# RC_Engine_Sound_ESP32.net
KiCad netlist of a schematic drawn in EAGLE
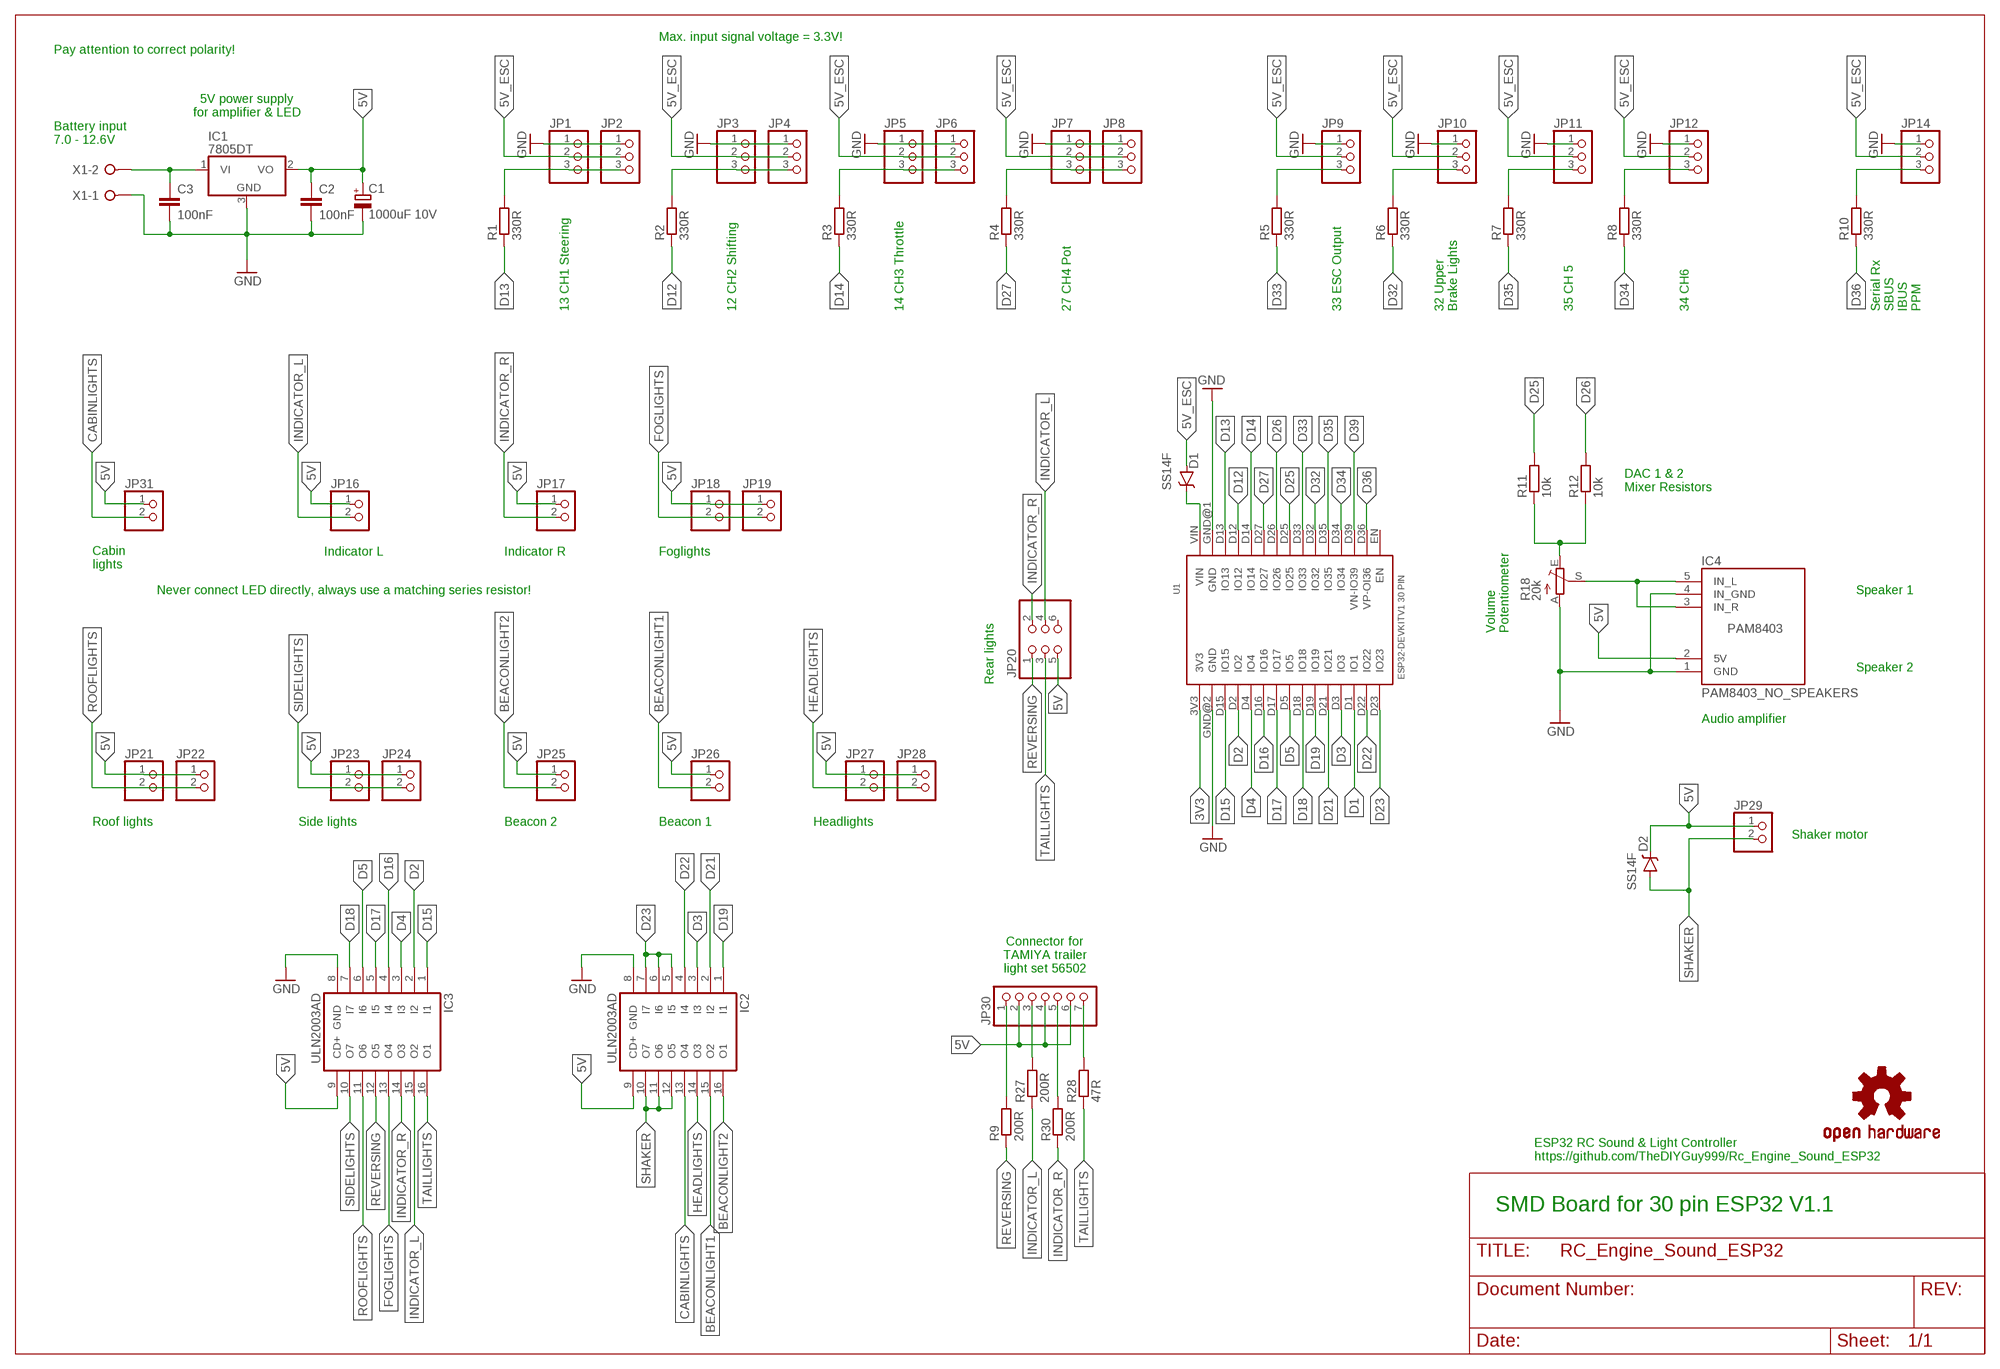
[diagram p0: schematic, sheet 1]

(export (version "E")
  (design (tool "Eeschema 10.0.6"))
  (components
    (comp (ref "C1")
      (value "1000uF 10V")
      (footprint "eagle-import:UD-10X10_NICHICON")
      (libsource (lib "eagle-import") (part "CPOL-EUUD-10X10"))
    )
    (comp (ref "C2")
      (value "100nF")
      (footprint "eagle-import:C0805")
      (libsource (lib "eagle-import") (part "C-EUC0805"))
    )
    (comp (ref "C3")
      (value "100nF")
      (footprint "eagle-import:C0805")
      (libsource (lib "eagle-import") (part "C-EUC0805"))
    )
    (comp (ref "D1")
      (value "SS14F")
      (footprint "eagle-import:SMA-DIODE")
      (libsource (lib "eagle-import") (part "MBRA140"))
    )
    (comp (ref "D2")
      (value "SS14F")
      (footprint "eagle-import:SMA-DIODE")
      (libsource (lib "eagle-import") (part "MBRA140"))
    )
    (comp (ref "IC1")
      (value "7805DT")
      (footprint "eagle-import:TO252")
      (libsource (lib "eagle-import") (part "78DT05"))
    )
    (comp (ref "IC2")
      (value "ULN2003AD")
      (footprint "eagle-import:SO16")
      (libsource (lib "eagle-import") (part "ULN2003AD"))
    )
    (comp (ref "IC3")
      (value "ULN2003AD")
      (footprint "eagle-import:SO16")
      (libsource (lib "eagle-import") (part "ULN2003AD"))
    )
    (comp (ref "IC4")
      (value "PAM8403_NO_SPEAKERS")
      (footprint "eagle-import:PAM8403_NO_SPEAKERS")
      (libsource (lib "eagle-import") (part "PAM8403_NO_SPEAKERS"))
    )
    (comp (ref "JP1")
      (value "PINHD-1X3")
      (footprint "eagle-import:1X03")
      (libsource (lib "eagle-import") (part "PINHD-1X3"))
    )
    (comp (ref "JP2")
      (value "PINHD-1X3")
      (footprint "eagle-import:1X03")
      (libsource (lib "eagle-import") (part "PINHD-1X3"))
    )
    (comp (ref "JP3")
      (value "PINHD-1X3")
      (footprint "eagle-import:1X03")
      (libsource (lib "eagle-import") (part "PINHD-1X3"))
    )
    (comp (ref "JP4")
      (value "PINHD-1X3")
      (footprint "eagle-import:1X03")
      (libsource (lib "eagle-import") (part "PINHD-1X3"))
    )
    (comp (ref "JP5")
      (value "PINHD-1X3")
      (footprint "eagle-import:1X03")
      (libsource (lib "eagle-import") (part "PINHD-1X3"))
    )
    (comp (ref "JP6")
      (value "PINHD-1X3")
      (footprint "eagle-import:1X03")
      (libsource (lib "eagle-import") (part "PINHD-1X3"))
    )
    (comp (ref "JP7")
      (value "PINHD-1X3")
      (footprint "eagle-import:1X03")
      (libsource (lib "eagle-import") (part "PINHD-1X3"))
    )
    (comp (ref "JP8")
      (value "PINHD-1X3")
      (footprint "eagle-import:1X03")
      (libsource (lib "eagle-import") (part "PINHD-1X3"))
    )
    (comp (ref "JP9")
      (value "PINHD-1X3")
      (footprint "eagle-import:1X03")
      (libsource (lib "eagle-import") (part "PINHD-1X3"))
    )
    (comp (ref "JP10")
      (value "PINHD-1X3")
      (footprint "eagle-import:1X03")
      (libsource (lib "eagle-import") (part "PINHD-1X3"))
    )
    (comp (ref "JP11")
      (value "PINHD-1X3")
      (footprint "eagle-import:1X03")
      (libsource (lib "eagle-import") (part "PINHD-1X3"))
    )
    (comp (ref "JP12")
      (value "PINHD-1X3")
      (footprint "eagle-import:1X03")
      (libsource (lib "eagle-import") (part "PINHD-1X3"))
    )
    (comp (ref "JP14")
      (value "PINHD-1X3")
      (footprint "eagle-import:1X03")
      (libsource (lib "eagle-import") (part "PINHD-1X3"))
    )
    (comp (ref "JP16")
      (value "PINHD-1X2")
      (footprint "eagle-import:1X02")
      (libsource (lib "eagle-import") (part "PINHD-1X2"))
    )
    (comp (ref "JP17")
      (value "PINHD-1X2")
      (footprint "eagle-import:1X02")
      (libsource (lib "eagle-import") (part "PINHD-1X2"))
    )
    (comp (ref "JP18")
      (value "PINHD-1X2")
      (footprint "eagle-import:1X02")
      (libsource (lib "eagle-import") (part "PINHD-1X2"))
    )
    (comp (ref "JP19")
      (value "PINHD-1X2")
      (footprint "eagle-import:1X02")
      (libsource (lib "eagle-import") (part "PINHD-1X2"))
    )
    (comp (ref "JP20")
      (value "PINHD-2X3")
      (footprint "eagle-import:2X03")
      (libsource (lib "eagle-import") (part "PINHD-2X3"))
    )
    (comp (ref "JP21")
      (value "PINHD-1X2")
      (footprint "eagle-import:1X02")
      (libsource (lib "eagle-import") (part "PINHD-1X2"))
    )
    (comp (ref "JP22")
      (value "PINHD-1X2")
      (footprint "eagle-import:1X02")
      (libsource (lib "eagle-import") (part "PINHD-1X2"))
    )
    (comp (ref "JP23")
      (value "PINHD-1X2")
      (footprint "eagle-import:1X02")
      (libsource (lib "eagle-import") (part "PINHD-1X2"))
    )
    (comp (ref "JP24")
      (value "PINHD-1X2")
      (footprint "eagle-import:1X02")
      (libsource (lib "eagle-import") (part "PINHD-1X2"))
    )
    (comp (ref "JP25")
      (value "PINHD-1X2")
      (footprint "eagle-import:1X02")
      (libsource (lib "eagle-import") (part "PINHD-1X2"))
    )
    (comp (ref "JP26")
      (value "PINHD-1X2")
      (footprint "eagle-import:1X02")
      (libsource (lib "eagle-import") (part "PINHD-1X2"))
    )
    (comp (ref "JP27")
      (value "PINHD-1X2")
      (footprint "eagle-import:1X02")
      (libsource (lib "eagle-import") (part "PINHD-1X2"))
    )
    (comp (ref "JP28")
      (value "PINHD-1X2")
      (footprint "eagle-import:1X02")
      (libsource (lib "eagle-import") (part "PINHD-1X2"))
    )
    (comp (ref "JP29")
      (value "PINHD-1X2")
      (footprint "eagle-import:1X02")
      (libsource (lib "eagle-import") (part "PINHD-1X2"))
    )
    (comp (ref "JP30")
      (value "PINHD-1X7")
      (footprint "eagle-import:1X07")
      (libsource (lib "eagle-import") (part "PINHD-1X7"))
    )
    (comp (ref "JP31")
      (value "PINHD-1X2")
      (footprint "eagle-import:1X02")
      (libsource (lib "eagle-import") (part "PINHD-1X2"))
    )
    (comp (ref "LOGO1")
      (value "OSHW-LOGOM")
      (footprint "eagle-import:OSHW-LOGO-M")
      (libsource (lib "eagle-import") (part "OSHW-LOGOM"))
    )
    (comp (ref "R1")
      (value "330R")
      (footprint "eagle-import:R0805")
      (libsource (lib "eagle-import") (part "R-EU_R0805"))
    )
    (comp (ref "R2")
      (value "330R")
      (footprint "eagle-import:R0805")
      (libsource (lib "eagle-import") (part "R-EU_R0805"))
    )
    (comp (ref "R3")
      (value "330R")
      (footprint "eagle-import:R0805")
      (libsource (lib "eagle-import") (part "R-EU_R0805"))
    )
    (comp (ref "R4")
      (value "330R")
      (footprint "eagle-import:R0805")
      (libsource (lib "eagle-import") (part "R-EU_R0805"))
    )
    (comp (ref "R5")
      (value "330R")
      (footprint "eagle-import:R0805")
      (libsource (lib "eagle-import") (part "R-EU_R0805"))
    )
    (comp (ref "R6")
      (value "330R")
      (footprint "eagle-import:R0805")
      (libsource (lib "eagle-import") (part "R-EU_R0805"))
    )
    (comp (ref "R7")
      (value "330R")
      (footprint "eagle-import:R0805")
      (libsource (lib "eagle-import") (part "R-EU_R0805"))
    )
    (comp (ref "R8")
      (value "330R")
      (footprint "eagle-import:R0805")
      (libsource (lib "eagle-import") (part "R-EU_R0805"))
    )
    (comp (ref "R9")
      (value "200R")
      (footprint "eagle-import:R0805")
      (libsource (lib "eagle-import") (part "R-EU_R0805"))
    )
    (comp (ref "R10")
      (value "330R")
      (footprint "eagle-import:R0805")
      (libsource (lib "eagle-import") (part "R-EU_R0805"))
    )
    (comp (ref "R11")
      (value "10k")
      (footprint "eagle-import:R0805")
      (libsource (lib "eagle-import") (part "R-EU_R0805"))
    )
    (comp (ref "R12")
      (value "10k")
      (footprint "eagle-import:R0805")
      (libsource (lib "eagle-import") (part "R-EU_R0805"))
    )
    (comp (ref "R18")
      (value "20k")
      (footprint "eagle-import:S64W")
      (libsource (lib "eagle-import") (part "TRIM_EU-S64W"))
    )
    (comp (ref "R27")
      (value "200R")
      (footprint "eagle-import:R0805")
      (libsource (lib "eagle-import") (part "R-EU_R0805"))
    )
    (comp (ref "R28")
      (value "47R")
      (footprint "eagle-import:R0805")
      (libsource (lib "eagle-import") (part "R-EU_R0805"))
    )
    (comp (ref "R30")
      (value "200R")
      (footprint "eagle-import:R0805")
      (libsource (lib "eagle-import") (part "R-EU_R0805"))
    )
    (comp (ref "U1")
      (value "ESP32DEVKITV1")
      (footprint "eagle-import:ESP32-DEVKITV1")
      (libsource (lib "eagle-import") (part "ESP32DEVKITV1"))
    )
    (comp (ref "X1")
      (value "W237-02P")
      (footprint "eagle-import:W237-132")
      (libsource (lib "eagle-import") (part "W237-02P"))
    )
  )
  (nets
    (net (code "1") (name "3V3") (class "Default")
      (node (ref "U1") (pin "3V3") (pinfunction "3V3_3V3") (pintype "bidirectional"))
    )
    (net (code "2") (name "5V") (class "Default")
      (node (ref "C1") (pin "+") (pinfunction "+_+") (pintype "passive"))
      (node (ref "C2") (pin "1") (pinfunction "1_1") (pintype "passive"))
      (node (ref "D2") (pin "C") (pinfunction "C_C") (pintype "passive"))
      (node (ref "IC1") (pin "2") (pinfunction "VO_2") (pintype "passive"))
      (node (ref "IC2") (pin "9") (pinfunction "CD+_9") (pintype "passive"))
      (node (ref "IC3") (pin "9") (pinfunction "CD+_9") (pintype "passive"))
      (node (ref "IC4") (pin "2") (pinfunction "5V_2") (pintype "input"))
      (node (ref "JP16") (pin "1") (pinfunction "1_1") (pintype "passive"))
      (node (ref "JP17") (pin "1") (pinfunction "1_1") (pintype "passive"))
      (node (ref "JP18") (pin "1") (pinfunction "1_1") (pintype "passive"))
      (node (ref "JP19") (pin "1") (pinfunction "1_1") (pintype "passive"))
      (node (ref "JP20") (pin "5") (pinfunction "5_5") (pintype "passive"))
      (node (ref "JP21") (pin "1") (pinfunction "1_1") (pintype "passive"))
      (node (ref "JP22") (pin "1") (pinfunction "1_1") (pintype "passive"))
      (node (ref "JP23") (pin "1") (pinfunction "1_1") (pintype "passive"))
      (node (ref "JP24") (pin "1") (pinfunction "1_1") (pintype "passive"))
      (node (ref "JP25") (pin "1") (pinfunction "1_1") (pintype "passive"))
      (node (ref "JP26") (pin "1") (pinfunction "1_1") (pintype "passive"))
      (node (ref "JP27") (pin "1") (pinfunction "1_1") (pintype "passive"))
      (node (ref "JP28") (pin "1") (pinfunction "1_1") (pintype "passive"))
      (node (ref "JP29") (pin "1") (pinfunction "1_1") (pintype "passive"))
      (node (ref "JP30") (pin "2") (pinfunction "2_2") (pintype "passive"))
      (node (ref "JP30") (pin "4") (pinfunction "4_4") (pintype "passive"))
      (node (ref "JP30") (pin "6") (pinfunction "6_6") (pintype "passive"))
      (node (ref "JP31") (pin "1") (pinfunction "1_1") (pintype "passive"))
    )
    (net (code "3") (name "5V_ESC") (class "Default")
      (node (ref "D1") (pin "A") (pinfunction "A_A") (pintype "passive"))
      (node (ref "JP1") (pin "2") (pinfunction "2_2") (pintype "passive"))
      (node (ref "JP10") (pin "2") (pinfunction "2_2") (pintype "passive"))
      (node (ref "JP11") (pin "2") (pinfunction "2_2") (pintype "passive"))
      (node (ref "JP12") (pin "2") (pinfunction "2_2") (pintype "passive"))
      (node (ref "JP14") (pin "2") (pinfunction "2_2") (pintype "passive"))
      (node (ref "JP2") (pin "2") (pinfunction "2_2") (pintype "passive"))
      (node (ref "JP3") (pin "2") (pinfunction "2_2") (pintype "passive"))
      (node (ref "JP4") (pin "2") (pinfunction "2_2") (pintype "passive"))
      (node (ref "JP5") (pin "2") (pinfunction "2_2") (pintype "passive"))
      (node (ref "JP6") (pin "2") (pinfunction "2_2") (pintype "passive"))
      (node (ref "JP7") (pin "2") (pinfunction "2_2") (pintype "passive"))
      (node (ref "JP8") (pin "2") (pinfunction "2_2") (pintype "passive"))
      (node (ref "JP9") (pin "2") (pinfunction "2_2") (pintype "passive"))
    )
    (net (code "4") (name "BEACONLIGHT1") (class "Default")
      (node (ref "IC2") (pin "15") (pinfunction "O2_15") (pintype "open_collector"))
      (node (ref "JP26") (pin "2") (pinfunction "2_2") (pintype "passive"))
    )
    (net (code "5") (name "BEACONLIGHT2") (class "Default")
      (node (ref "IC2") (pin "16") (pinfunction "O1_16") (pintype "open_collector"))
      (node (ref "JP25") (pin "2") (pinfunction "2_2") (pintype "passive"))
    )
    (net (code "6") (name "CABINLIGHTS") (class "Default")
      (node (ref "IC2") (pin "13") (pinfunction "O4_13") (pintype "open_collector"))
      (node (ref "JP31") (pin "2") (pinfunction "2_2") (pintype "passive"))
    )
    (net (code "7") (name "D1") (class "Default")
      (node (ref "U1") (pin "D1") (pinfunction "IO1_D1") (pintype "bidirectional"))
    )
    (net (code "8") (name "D2") (class "Default")
      (node (ref "IC3") (pin "2") (pinfunction "I2_2") (pintype "input"))
      (node (ref "U1") (pin "D2") (pinfunction "IO2_D2") (pintype "bidirectional"))
    )
    (net (code "9") (name "D3") (class "Default")
      (node (ref "IC2") (pin "3") (pinfunction "I3_3") (pintype "input"))
      (node (ref "U1") (pin "D3") (pinfunction "IO3_D3") (pintype "bidirectional"))
    )
    (net (code "10") (name "D4") (class "Default")
      (node (ref "IC3") (pin "3") (pinfunction "I3_3") (pintype "input"))
      (node (ref "U1") (pin "D4") (pinfunction "IO4_D4") (pintype "bidirectional"))
    )
    (net (code "11") (name "D5") (class "Default")
      (node (ref "IC3") (pin "6") (pinfunction "I6_6") (pintype "input"))
      (node (ref "U1") (pin "D5") (pinfunction "IO5_D5") (pintype "bidirectional"))
    )
    (net (code "12") (name "D12") (class "Default")
      (node (ref "R2") (pin "1") (pinfunction "1_1") (pintype "passive"))
      (node (ref "U1") (pin "D12") (pinfunction "IO12_D12") (pintype "bidirectional"))
    )
    (net (code "13") (name "D13") (class "Default")
      (node (ref "R1") (pin "1") (pinfunction "1_1") (pintype "passive"))
      (node (ref "U1") (pin "D13") (pinfunction "IO13_D13") (pintype "bidirectional"))
    )
    (net (code "14") (name "D14") (class "Default")
      (node (ref "R3") (pin "1") (pinfunction "1_1") (pintype "passive"))
      (node (ref "U1") (pin "D14") (pinfunction "IO14_D14") (pintype "bidirectional"))
    )
    (net (code "15") (name "D15") (class "Default")
      (node (ref "IC3") (pin "1") (pinfunction "I1_1") (pintype "input"))
      (node (ref "U1") (pin "D15") (pinfunction "IO15_D15") (pintype "bidirectional"))
    )
    (net (code "16") (name "D16") (class "Default")
      (node (ref "IC3") (pin "4") (pinfunction "I4_4") (pintype "input"))
      (node (ref "U1") (pin "D16") (pinfunction "IO16_D16") (pintype "bidirectional"))
    )
    (net (code "17") (name "D17") (class "Default")
      (node (ref "IC3") (pin "5") (pinfunction "I5_5") (pintype "input"))
      (node (ref "U1") (pin "D17") (pinfunction "IO17_D17") (pintype "bidirectional"))
    )
    (net (code "18") (name "D18") (class "Default")
      (node (ref "IC3") (pin "7") (pinfunction "I7_7") (pintype "input"))
      (node (ref "U1") (pin "D18") (pinfunction "IO18_D18") (pintype "bidirectional"))
    )
    (net (code "19") (name "D19") (class "Default")
      (node (ref "IC2") (pin "1") (pinfunction "I1_1") (pintype "input"))
      (node (ref "U1") (pin "D19") (pinfunction "IO19_D19") (pintype "bidirectional"))
    )
    (net (code "20") (name "D21") (class "Default")
      (node (ref "IC2") (pin "2") (pinfunction "I2_2") (pintype "input"))
      (node (ref "U1") (pin "D21") (pinfunction "IO21_D21") (pintype "bidirectional"))
    )
    (net (code "21") (name "D22") (class "Default")
      (node (ref "IC2") (pin "4") (pinfunction "I4_4") (pintype "input"))
      (node (ref "U1") (pin "D22") (pinfunction "IO22_D22") (pintype "bidirectional"))
    )
    (net (code "22") (name "D23") (class "Default")
      (node (ref "IC2") (pin "5") (pinfunction "I5_5") (pintype "input"))
      (node (ref "IC2") (pin "6") (pinfunction "I6_6") (pintype "input"))
      (node (ref "IC2") (pin "7") (pinfunction "I7_7") (pintype "input"))
      (node (ref "U1") (pin "D23") (pinfunction "IO23_D23") (pintype "bidirectional"))
    )
    (net (code "23") (name "D25") (class "Default")
      (node (ref "R11") (pin "2") (pinfunction "2_2") (pintype "passive"))
      (node (ref "U1") (pin "D25") (pinfunction "IO25_D25") (pintype "bidirectional"))
    )
    (net (code "24") (name "D26") (class "Default")
      (node (ref "R12") (pin "2") (pinfunction "2_2") (pintype "passive"))
      (node (ref "U1") (pin "D26") (pinfunction "IO26_D26") (pintype "bidirectional"))
    )
    (net (code "25") (name "D27") (class "Default")
      (node (ref "R4") (pin "1") (pinfunction "1_1") (pintype "passive"))
      (node (ref "U1") (pin "D27") (pinfunction "IO27_D27") (pintype "bidirectional"))
    )
    (net (code "26") (name "D32") (class "Default")
      (node (ref "R6") (pin "1") (pinfunction "1_1") (pintype "passive"))
      (node (ref "U1") (pin "D32") (pinfunction "IO32_D32") (pintype "bidirectional"))
    )
    (net (code "27") (name "D33") (class "Default")
      (node (ref "R5") (pin "1") (pinfunction "1_1") (pintype "passive"))
      (node (ref "U1") (pin "D33") (pinfunction "IO33_D33") (pintype "bidirectional"))
    )
    (net (code "28") (name "D34") (class "Default")
      (node (ref "R8") (pin "1") (pinfunction "1_1") (pintype "passive"))
      (node (ref "U1") (pin "D34") (pinfunction "IO34_D34") (pintype "bidirectional"))
    )
    (net (code "29") (name "D35") (class "Default")
      (node (ref "R7") (pin "1") (pinfunction "1_1") (pintype "passive"))
      (node (ref "U1") (pin "D35") (pinfunction "IO35_D35") (pintype "bidirectional"))
    )
    (net (code "30") (name "D36") (class "Default")
      (node (ref "R10") (pin "1") (pinfunction "1_1") (pintype "passive"))
      (node (ref "U1") (pin "D36") (pinfunction "VP-OI36_D36") (pintype "bidirectional"))
    )
    (net (code "31") (name "D39") (class "Default")
      (node (ref "U1") (pin "D39") (pinfunction "VN-IO39_D39") (pintype "bidirectional"))
    )
    (net (code "32") (name "FOGLIGHTS") (class "Default")
      (node (ref "IC3") (pin "13") (pinfunction "O4_13") (pintype "open_collector"))
      (node (ref "JP18") (pin "2") (pinfunction "2_2") (pintype "passive"))
      (node (ref "JP19") (pin "2") (pinfunction "2_2") (pintype "passive"))
    )
    (net (code "33") (name "GND") (class "Default")
      (node (ref "C1") (pin "-") (pinfunction "-_-") (pintype "passive"))
      (node (ref "C2") (pin "2") (pinfunction "2_2") (pintype "passive"))
      (node (ref "C3") (pin "2") (pinfunction "2_2") (pintype "passive"))
      (node (ref "IC1") (pin "3") (pinfunction "GND_3") (pintype "passive"))
      (node (ref "IC2") (pin "8") (pinfunction "GND_8") (pintype "power_in"))
      (node (ref "IC3") (pin "8") (pinfunction "GND_8") (pintype "power_in"))
      (node (ref "IC4") (pin "1") (pinfunction "GND_1") (pintype "input"))
      (node (ref "IC4") (pin "4") (pinfunction "IN_GND_4") (pintype "input"))
      (node (ref "JP1") (pin "1") (pinfunction "1_1") (pintype "passive"))
      (node (ref "JP10") (pin "1") (pinfunction "1_1") (pintype "passive"))
      (node (ref "JP11") (pin "1") (pinfunction "1_1") (pintype "passive"))
      (node (ref "JP12") (pin "1") (pinfunction "1_1") (pintype "passive"))
      (node (ref "JP14") (pin "1") (pinfunction "1_1") (pintype "passive"))
      (node (ref "JP2") (pin "1") (pinfunction "1_1") (pintype "passive"))
      (node (ref "JP3") (pin "1") (pinfunction "1_1") (pintype "passive"))
      (node (ref "JP4") (pin "1") (pinfunction "1_1") (pintype "passive"))
      (node (ref "JP5") (pin "1") (pinfunction "1_1") (pintype "passive"))
      (node (ref "JP6") (pin "1") (pinfunction "1_1") (pintype "passive"))
      (node (ref "JP7") (pin "1") (pinfunction "1_1") (pintype "passive"))
      (node (ref "JP8") (pin "1") (pinfunction "1_1") (pintype "passive"))
      (node (ref "JP9") (pin "1") (pinfunction "1_1") (pintype "passive"))
      (node (ref "R18") (pin "A") (pinfunction "A_A") (pintype "passive"))
      (node (ref "U1") (pin "GND@1") (pinfunction "GND_GND@1") (pintype "bidirectional"))
      (node (ref "U1") (pin "GND@2") (pinfunction "GND_GND@2") (pintype "bidirectional"))
      (node (ref "X1") (pin "1") (pinfunction "KL_1") (pintype "passive"))
    )
    (net (code "34") (name "HEADLIGHTS") (class "Default")
      (node (ref "IC2") (pin "14") (pinfunction "O3_14") (pintype "open_collector"))
      (node (ref "JP27") (pin "2") (pinfunction "2_2") (pintype "passive"))
      (node (ref "JP28") (pin "2") (pinfunction "2_2") (pintype "passive"))
    )
    (net (code "35") (name "INDICATOR_L") (class "Default")
      (node (ref "IC3") (pin "15") (pinfunction "O2_15") (pintype "open_collector"))
      (node (ref "JP16") (pin "2") (pinfunction "2_2") (pintype "passive"))
      (node (ref "JP20") (pin "4") (pinfunction "4_4") (pintype "passive"))
      (node (ref "R27") (pin "1") (pinfunction "1_1") (pintype "passive"))
    )
    (net (code "36") (name "INDICATOR_R") (class "Default")
      (node (ref "IC3") (pin "14") (pinfunction "O3_14") (pintype "open_collector"))
      (node (ref "JP17") (pin "2") (pinfunction "2_2") (pintype "passive"))
      (node (ref "JP20") (pin "2") (pinfunction "2_2") (pintype "passive"))
      (node (ref "R30") (pin "1") (pinfunction "1_1") (pintype "passive"))
    )
    (net (code "37") (name "Net-(D1-PadC)") (class "Default")
      (node (ref "D1") (pin "C") (pinfunction "C_C") (pintype "passive"))
      (node (ref "U1") (pin "VIN") (pinfunction "VIN_VIN") (pintype "bidirectional"))
    )
    (net (code "38") (name "Net-(IC1-VI)") (class "Default")
      (node (ref "C3") (pin "1") (pinfunction "1_1") (pintype "passive"))
      (node (ref "IC1") (pin "1") (pinfunction "VI_1") (pintype "input"))
      (node (ref "X1") (pin "2") (pinfunction "KL_2") (pintype "passive"))
    )
    (net (code "39") (name "Net-(IC4-IN_L)") (class "Default")
      (node (ref "IC4") (pin "3") (pinfunction "IN_R_3") (pintype "input"))
      (node (ref "IC4") (pin "5") (pinfunction "IN_L_5") (pintype "input"))
      (node (ref "R18") (pin "S") (pinfunction "S_S") (pintype "passive"))
    )
    (net (code "40") (name "Net-(JP1-Pad3)") (class "Default")
      (node (ref "JP1") (pin "3") (pinfunction "3_3") (pintype "passive"))
      (node (ref "JP2") (pin "3") (pinfunction "3_3") (pintype "passive"))
      (node (ref "R1") (pin "2") (pinfunction "2_2") (pintype "passive"))
    )
    (net (code "41") (name "Net-(JP3-Pad3)") (class "Default")
      (node (ref "JP3") (pin "3") (pinfunction "3_3") (pintype "passive"))
      (node (ref "JP4") (pin "3") (pinfunction "3_3") (pintype "passive"))
      (node (ref "R2") (pin "2") (pinfunction "2_2") (pintype "passive"))
    )
    (net (code "42") (name "Net-(JP5-Pad3)") (class "Default")
      (node (ref "JP5") (pin "3") (pinfunction "3_3") (pintype "passive"))
      (node (ref "JP6") (pin "3") (pinfunction "3_3") (pintype "passive"))
      (node (ref "R3") (pin "2") (pinfunction "2_2") (pintype "passive"))
    )
    (net (code "43") (name "Net-(JP7-Pad3)") (class "Default")
      (node (ref "JP7") (pin "3") (pinfunction "3_3") (pintype "passive"))
      (node (ref "JP8") (pin "3") (pinfunction "3_3") (pintype "passive"))
      (node (ref "R4") (pin "2") (pinfunction "2_2") (pintype "passive"))
    )
    (net (code "44") (name "Net-(JP9-Pad3)") (class "Default")
      (node (ref "JP9") (pin "3") (pinfunction "3_3") (pintype "passive"))
      (node (ref "R5") (pin "2") (pinfunction "2_2") (pintype "passive"))
    )
    (net (code "45") (name "Net-(JP10-Pad3)") (class "Default")
      (node (ref "JP10") (pin "3") (pinfunction "3_3") (pintype "passive"))
      (node (ref "R6") (pin "2") (pinfunction "2_2") (pintype "passive"))
    )
    (net (code "46") (name "Net-(JP11-Pad3)") (class "Default")
      (node (ref "JP11") (pin "3") (pinfunction "3_3") (pintype "passive"))
      (node (ref "R7") (pin "2") (pinfunction "2_2") (pintype "passive"))
    )
    (net (code "47") (name "Net-(JP12-Pad3)") (class "Default")
      (node (ref "JP12") (pin "3") (pinfunction "3_3") (pintype "passive"))
      (node (ref "R8") (pin "2") (pinfunction "2_2") (pintype "passive"))
    )
    (net (code "48") (name "Net-(JP14-Pad3)") (class "Default")
      (node (ref "JP14") (pin "3") (pinfunction "3_3") (pintype "passive"))
      (node (ref "R10") (pin "2") (pinfunction "2_2") (pintype "passive"))
    )
    (net (code "49") (name "Net-(JP30-Pad1)") (class "Default")
      (node (ref "JP30") (pin "1") (pinfunction "1_1") (pintype "passive"))
      (node (ref "R9") (pin "2") (pinfunction "2_2") (pintype "passive"))
    )
    (net (code "50") (name "Net-(JP30-Pad3)") (class "Default")
      (node (ref "JP30") (pin "3") (pinfunction "3_3") (pintype "passive"))
      (node (ref "R27") (pin "2") (pinfunction "2_2") (pintype "passive"))
    )
    (net (code "51") (name "Net-(JP30-Pad5)") (class "Default")
      (node (ref "JP30") (pin "5") (pinfunction "5_5") (pintype "passive"))
      (node (ref "R30") (pin "2") (pinfunction "2_2") (pintype "passive"))
    )
    (net (code "52") (name "Net-(JP30-Pad7)") (class "Default")
      (node (ref "JP30") (pin "7") (pinfunction "7_7") (pintype "passive"))
      (node (ref "R28") (pin "2") (pinfunction "2_2") (pintype "passive"))
    )
    (net (code "53") (name "Net-(R11-Pad1)") (class "Default")
      (node (ref "R11") (pin "1") (pinfunction "1_1") (pintype "passive"))
      (node (ref "R12") (pin "1") (pinfunction "1_1") (pintype "passive"))
      (node (ref "R18") (pin "E") (pinfunction "E_E") (pintype "passive"))
    )
    (net (code "54") (name "REVERSING") (class "Default")
      (node (ref "IC3") (pin "12") (pinfunction "O5_12") (pintype "open_collector"))
      (node (ref "JP20") (pin "1") (pinfunction "1_1") (pintype "passive"))
      (node (ref "R9") (pin "1") (pinfunction "1_1") (pintype "passive"))
    )
    (net (code "55") (name "ROOFLIGHTS") (class "Default")
      (node (ref "IC3") (pin "11") (pinfunction "O6_11") (pintype "open_collector"))
      (node (ref "JP21") (pin "2") (pinfunction "2_2") (pintype "passive"))
      (node (ref "JP22") (pin "2") (pinfunction "2_2") (pintype "passive"))
    )
    (net (code "56") (name "SHAKER") (class "Default")
      (node (ref "D2") (pin "A") (pinfunction "A_A") (pintype "passive"))
      (node (ref "IC2") (pin "10") (pinfunction "O7_10") (pintype "open_collector"))
      (node (ref "IC2") (pin "11") (pinfunction "O6_11") (pintype "open_collector"))
      (node (ref "IC2") (pin "12") (pinfunction "O5_12") (pintype "open_collector"))
      (node (ref "JP29") (pin "2") (pinfunction "2_2") (pintype "passive"))
    )
    (net (code "57") (name "SIDELIGHTS") (class "Default")
      (node (ref "IC3") (pin "10") (pinfunction "O7_10") (pintype "open_collector"))
      (node (ref "JP23") (pin "2") (pinfunction "2_2") (pintype "passive"))
      (node (ref "JP24") (pin "2") (pinfunction "2_2") (pintype "passive"))
    )
    (net (code "58") (name "TAILLIGHTS") (class "Default")
      (node (ref "IC3") (pin "16") (pinfunction "O1_16") (pintype "open_collector"))
      (node (ref "JP20") (pin "3") (pinfunction "3_3") (pintype "passive"))
      (node (ref "R28") (pin "1") (pinfunction "1_1") (pintype "passive"))
    )
    (net (code "59") (name "unconnected-(JP20-Pad6)") (class "Default")
      (node (ref "JP20") (pin "6") (pinfunction "6_6") (pintype "passive"))
    )
    (net (code "60") (name "unconnected-(U1-PadEN)") (class "Default")
      (node (ref "U1") (pin "EN") (pinfunction "EN_EN") (pintype "bidirectional"))
    )
  )
)
